# OS-2024-Badge-Schematic-REV0.net
KiCad netlist of a schematic drawn in Altium Designer
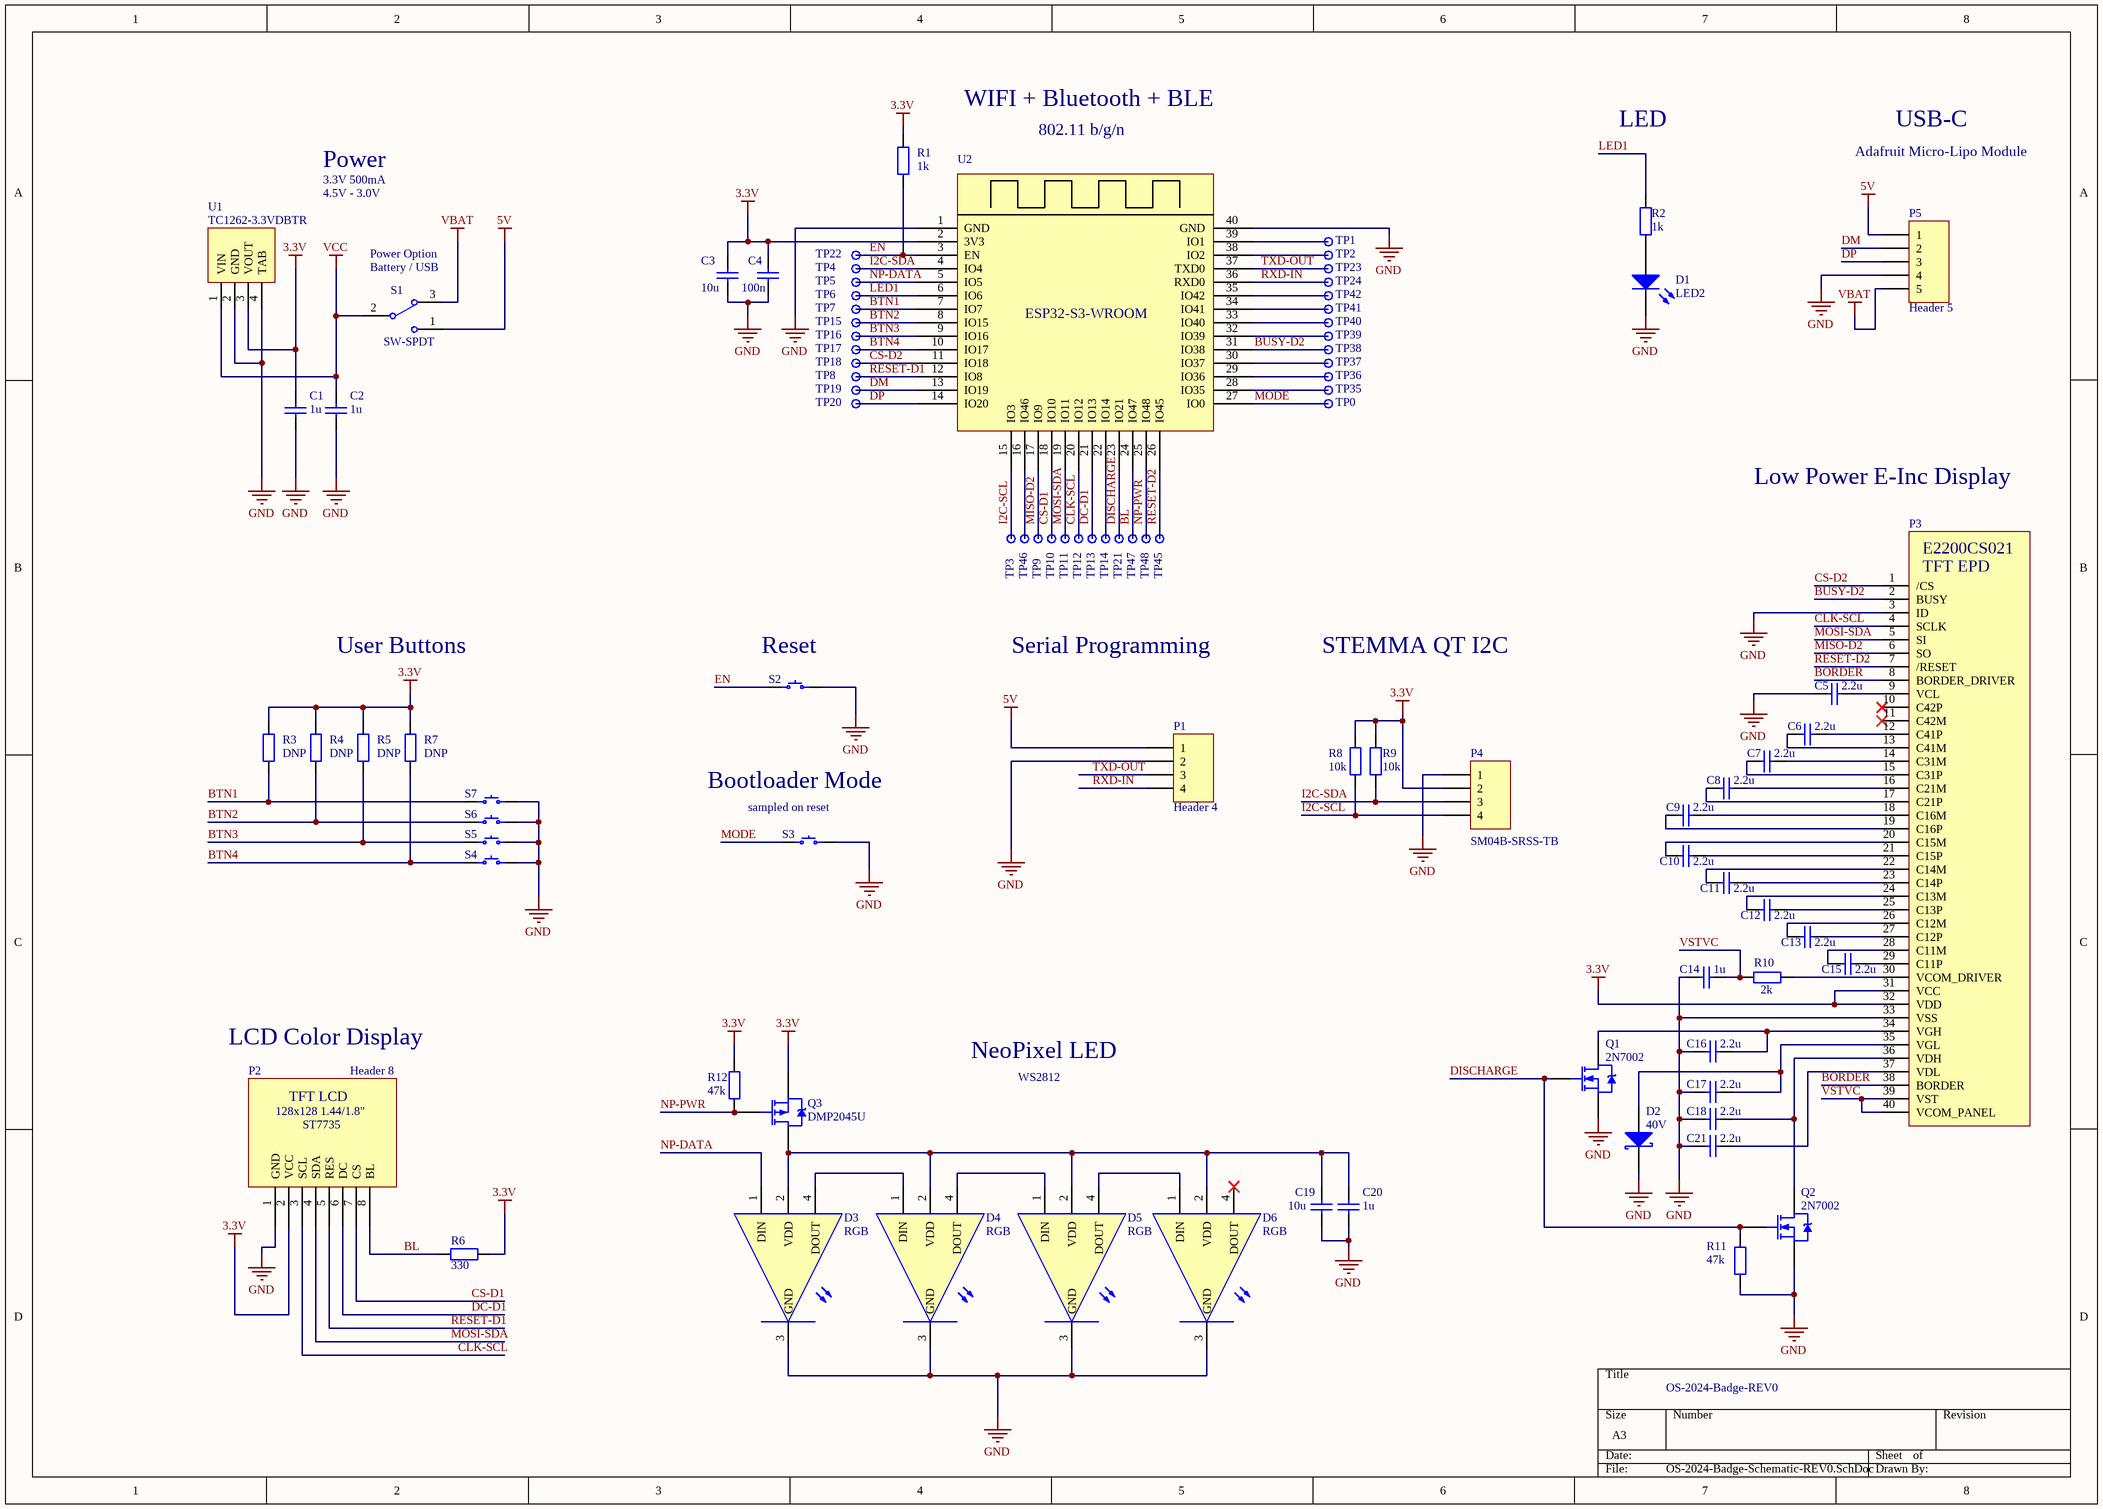
[diagram p0: OS-2024-Badge-Schematic-REV0.SchDoc]

(export (version "E")
  (design (tool "Eeschema 10.0.6"))
  (components
    (comp (ref "C1")
      (value "1u")
      (footprint "0603C")
      (description "CAP CER 1UF 50V Z5U 0603")
      (fields
        (field (name "MANUFACTURER") "Murata Electronics North America")
        (field (name "MANUFACTURER PART NUMBER") "GRT188R61H105ME13D")
      )
      (libsource (lib "Miscellaneous Devices") (part "Cap"))
    )
    (comp (ref "C2")
      (value "1u")
      (footprint "0603C")
      (description "CAP CER 1UF 50V Z5U 0603")
      (fields
        (field (name "MANUFACTURER") "Murata Electronics North America")
        (field (name "MANUFACTURER PART NUMBER") "GRT188R61H105ME13D")
      )
      (libsource (lib "Miscellaneous Devices") (part "Cap"))
    )
    (comp (ref "C3")
      (value "10u")
      (footprint "0603C")
      (description "CAP CER 10UF 10V X5R 0603")
      (fields
        (field (name "MANUFACTURER") "Murata Electronics North America")
        (field (name "MANUFACTURER PART NUMBER") "GRN188R61A106KE69J")
      )
      (libsource (lib "Miscellaneous Devices") (part "Cap"))
    )
    (comp (ref "C4")
      (value "100n")
      (footprint "0603C")
      (description "CAP CER .1UF 10V X7R 0603")
      (fields
        (field (name "MANUFACTURER") "Wurth Electronics Inc.")
        (field (name "MANUFACTURER PART NUMBER") "885012206020")
      )
      (libsource (lib "Miscellaneous Devices") (part "Cap"))
    )
    (comp (ref "C5")
      (value "2.2u")
      (footprint "0603C")
      (description "CAP CER 2.2UF 10V X5R 0603")
      (fields
        (field (name "MANUFACTURER") "Cal-Chip Electronics, Inc.")
        (field (name "MANUFACTURER PART NUMBER") "GMC10X5R225M10NT")
      )
      (libsource (lib "Miscellaneous Devices") (part "Cap"))
    )
    (comp (ref "C6")
      (value "2.2u")
      (footprint "0603C")
      (description "CAP CER 2.2UF 10V X5R 0603")
      (fields
        (field (name "MANUFACTURER") "Cal-Chip Electronics, Inc.")
        (field (name "MANUFACTURER PART NUMBER") "GMC10X5R225M10NT")
      )
      (libsource (lib "Miscellaneous Devices") (part "Cap"))
    )
    (comp (ref "C7")
      (value "2.2u")
      (footprint "0603C")
      (description "CAP CER 2.2UF 10V X5R 0603")
      (fields
        (field (name "MANUFACTURER") "Cal-Chip Electronics, Inc.")
        (field (name "MANUFACTURER PART NUMBER") "GMC10X5R225M10NT")
      )
      (libsource (lib "Miscellaneous Devices") (part "Cap"))
    )
    (comp (ref "C8")
      (value "2.2u")
      (footprint "0603C")
      (description "CAP CER 2.2UF 10V X5R 0603")
      (fields
        (field (name "MANUFACTURER") "Cal-Chip Electronics, Inc.")
        (field (name "MANUFACTURER PART NUMBER") "GMC10X5R225M10NT")
      )
      (libsource (lib "Miscellaneous Devices") (part "Cap"))
    )
    (comp (ref "C9")
      (value "2.2u")
      (footprint "0603C")
      (description "CAP CER 2.2UF 10V X5R 0603")
      (fields
        (field (name "MANUFACTURER") "Cal-Chip Electronics, Inc.")
        (field (name "MANUFACTURER PART NUMBER") "GMC10X5R225M10NT")
      )
      (libsource (lib "Miscellaneous Devices") (part "Cap"))
    )
    (comp (ref "C10")
      (value "2.2u")
      (footprint "0603C")
      (description "CAP CER 2.2UF 10V X5R 0603")
      (fields
        (field (name "MANUFACTURER") "Cal-Chip Electronics, Inc.")
        (field (name "MANUFACTURER PART NUMBER") "GMC10X5R225M10NT")
      )
      (libsource (lib "Miscellaneous Devices") (part "Cap"))
    )
    (comp (ref "C11")
      (value "2.2u")
      (footprint "0603C")
      (description "CAP CER 2.2UF 10V X5R 0603")
      (fields
        (field (name "MANUFACTURER") "Cal-Chip Electronics, Inc.")
        (field (name "MANUFACTURER PART NUMBER") "GMC10X5R225M10NT")
      )
      (libsource (lib "Miscellaneous Devices") (part "Cap"))
    )
    (comp (ref "C12")
      (value "2.2u")
      (footprint "0603C")
      (description "CAP CER 2.2UF 10V X5R 0603")
      (fields
        (field (name "MANUFACTURER") "Cal-Chip Electronics, Inc.")
        (field (name "MANUFACTURER PART NUMBER") "GMC10X5R225M10NT")
      )
      (libsource (lib "Miscellaneous Devices") (part "Cap"))
    )
    (comp (ref "C13")
      (value "2.2u")
      (footprint "0603C")
      (description "CAP CER 2.2UF 10V X5R 0603")
      (fields
        (field (name "MANUFACTURER") "Cal-Chip Electronics, Inc.")
        (field (name "MANUFACTURER PART NUMBER") "GMC10X5R225M10NT")
      )
      (libsource (lib "Miscellaneous Devices") (part "Cap"))
    )
    (comp (ref "C14")
      (value "1u")
      (footprint "0603C")
      (description "CAP CER 1UF 50V Z5U 0603")
      (fields
        (field (name "MANUFACTURER") "Murata Electronics North America")
        (field (name "MANUFACTURER PART NUMBER") "GRT188R61H105ME13D")
      )
      (libsource (lib "Miscellaneous Devices") (part "Cap"))
    )
    (comp (ref "C15")
      (value "2.2u")
      (footprint "0603C")
      (description "CAP CER 2.2UF 10V X5R 0603")
      (fields
        (field (name "MANUFACTURER") "Cal-Chip Electronics, Inc.")
        (field (name "MANUFACTURER PART NUMBER") "GMC10X5R225M10NT")
      )
      (libsource (lib "Miscellaneous Devices") (part "Cap"))
    )
    (comp (ref "C16")
      (value "2.2u")
      (footprint "0603C")
      (description "CAP CER 2.2UF 10V X5R 0603")
      (fields
        (field (name "MANUFACTURER") "Cal-Chip Electronics, Inc.")
        (field (name "MANUFACTURER PART NUMBER") "GMC10X5R225M10NT")
      )
      (libsource (lib "Miscellaneous Devices") (part "Cap"))
    )
    (comp (ref "C17")
      (value "2.2u")
      (footprint "0603C")
      (description "CAP CER 2.2UF 10V X5R 0603")
      (fields
        (field (name "MANUFACTURER") "Cal-Chip Electronics, Inc.")
        (field (name "MANUFACTURER PART NUMBER") "GMC10X5R225M10NT")
      )
      (libsource (lib "Miscellaneous Devices") (part "Cap"))
    )
    (comp (ref "C18")
      (value "2.2u")
      (footprint "0603C")
      (description "CAP CER 2.2UF 10V X5R 0603")
      (fields
        (field (name "MANUFACTURER") "Cal-Chip Electronics, Inc.")
        (field (name "MANUFACTURER PART NUMBER") "GMC10X5R225M10NT")
      )
      (libsource (lib "Miscellaneous Devices") (part "Cap"))
    )
    (comp (ref "C19")
      (value "10u")
      (footprint "0603C")
      (description "CAP CER 10UF 10V X5R 0603")
      (fields
        (field (name "MANUFACTURER") "Murata Electronics North America")
        (field (name "MANUFACTURER PART NUMBER") "GRN188R61A106KE69J")
      )
      (libsource (lib "Miscellaneous Devices") (part "Cap"))
    )
    (comp (ref "C20")
      (value "1u")
      (footprint "0603C")
      (description "CAP CER 1UF 50V Z5U 0603")
      (fields
        (field (name "MANUFACTURER") "Murata Electronics North America")
        (field (name "MANUFACTURER PART NUMBER") "GRT188R61H105ME13D")
      )
      (libsource (lib "Miscellaneous Devices") (part "Cap"))
    )
    (comp (ref "C21")
      (value "2.2u")
      (footprint "0603C")
      (description "CAP CER 2.2UF 10V X5R 0603")
      (fields
        (field (name "MANUFACTURER") "Cal-Chip Electronics, Inc.")
        (field (name "MANUFACTURER PART NUMBER") "GMC10X5R225M10NT")
      )
      (libsource (lib "Miscellaneous Devices") (part "Cap"))
    )
    (comp (ref "D1")
      (value "LED2")
      (footprint "0603LED")
      (description "LED ORANGE CLEAR CHIP SMD")
      (fields
        (field (name "DISTRIBUTOR PART NUMBER") "754-1120-1-ND")
        (field (name "MANUFACTURER") "Kingbright")
      )
      (libsource (lib "Miscellaneous Devices") (part "LED2"))
    )
    (comp (ref "D2")
      (value "40V")
      (footprint "SOD-123FL")
      (description "DIODE SCHOTTKY 40V 2A SOD123FL")
      (fields
        (field (name "DISTRIBUTOR PART NUMBER") "3757-SS2040FL_R1_00001CT-ND")
        (field (name "MANUFACTURER") "Panjit International Inc.")
      )
      (libsource (lib "Miscellaneous Devices") (part "Diode BAT17"))
    )
    (comp (ref "D3")
      (value "RGB")
      (footprint "COM-12986")
      (description "ADDRESS LED DISCR SERIAL RGB")
      (fields
        (field (name "DISTRIBUTOR PART NUMBER") "1568-1213-ND")
        (field (name "MANUFACTURER") "Spark Fun")
      )
      (libsource (lib "2024-Badge-Altium-Project-REV0_1") (part "LED2_1"))
    )
    (comp (ref "D4")
      (value "RGB")
      (footprint "COM-12986")
      (description "ADDRESS LED DISCR SERIAL RGB")
      (fields
        (field (name "DISTRIBUTOR PART NUMBER") "1568-1213-ND")
        (field (name "MANUFACTURER") "Spark Fun")
      )
      (libsource (lib "2024-Badge-Altium-Project-REV0_1") (part "LED2_1"))
    )
    (comp (ref "D5")
      (value "RGB")
      (footprint "COM-12986")
      (description "ADDRESS LED DISCR SERIAL RGB")
      (fields
        (field (name "DISTRIBUTOR PART NUMBER") "1568-1213-ND")
        (field (name "MANUFACTURER") "Spark Fun")
      )
      (libsource (lib "2024-Badge-Altium-Project-REV0_1") (part "LED2_1"))
    )
    (comp (ref "D6")
      (value "RGB")
      (footprint "COM-12986")
      (description "ADDRESS LED DISCR SERIAL RGB")
      (fields
        (field (name "DISTRIBUTOR PART NUMBER") "1568-1213-ND")
        (field (name "MANUFACTURER") "Spark Fun")
      )
      (libsource (lib "2024-Badge-Altium-Project-REV0_1") (part "LED2_1"))
    )
    (comp (ref "P1")
      (value "Header 4")
      (footprint "HDR1X4")
      (description "Header, 4-Pin")
      (fields
        (field (name "DISTRIBUTOR PART NUMBER") "732-5317-ND")
        (field (name "MANUFACTURER") "Wurth Elektronik")
      )
      (libsource (lib "Miscellaneous Connectors") (part "Header 4"))
    )
    (comp (ref "P2")
      (value "Header 8")
      (footprint "TFT144SPI")
      (description "1.44\" 128x128 65K SPI Full Color TFT LCD Display Module ST7735 OLED for Arduino")
      (fields (field (name "DISTRIBUTOR PART NUMBER") "ED90446-ND") (field (name "MANUFACTURER") "Mill-Max"))
      (libsource (lib "OS-2019-Badge-Schematic-REV0") (part "Display_128_128"))
    )
    (comp (ref "P3")
      (value "CONN FPC TOP 40POS 0.5MM R/A")
      (footprint "AMPHENOL_62684-402100ALF")
      (fields
        (field (name "DISTRIBUTOR PART NUMBER") "609-1200-1-ND")
        (field (name "MANUFACTURER") "Amphenol ICC (FCI)")
        (field (name "MANUFACTURER PART NUMBER") "62684-402100ALF")
      )
      (libsource (lib "2024-Badge-Altium-Project-REV0_1") (part "Header 40"))
    )
    (comp (ref "P4")
      (value "SM04B-SRSS-TB")
      (footprint "SM04B-TRSS-TB")
      (description "CONN HEADER SMD R/A 4POS 1MM")
      (fields
        (field (name "DISTRIBUTOR PART NUMBER") "455-SM04B-SRSS-TBCT-ND")
        (field (name "MANUFACTURER") "JST Sales America Inc.")
      )
      (libsource (lib "2024-Badge-Altium-Project-REV0_1") (part "Header 5"))
    )
    (comp (ref "P5")
      (value "Header 5")
      (footprint "Micro-Lipo-USBC")
      (description "Adafruit Micro-Lipo Charger for LiPoly Batt with USB Type C Jack")
      (fields (field (name "DISTRIBUTOR PART NUMBER") "ED90446-ND") (field (name "MANUFACTURER") "Mill-Max"))
      (libsource (lib "Miscellaneous Connectors") (part "Header 5"))
    )
    (comp (ref "Q1")
      (value "2N7002")
      (footprint "SOT-23-N")
      (description "MOSFET N-CH 60V 280MA SOT23-3")
      (fields
        (field (name "DISTRIBUTOR PART NUMBER") "4878-2N7002CT-ND")
        (field (name "MANUFACTURER") "Diotec Semiconductor")
      )
      (libsource (lib "Miscellaneous Devices") (part "NMOS-2"))
    )
    (comp (ref "Q2")
      (value "2N7002")
      (footprint "SOT-23-N")
      (description "MOSFET N-CH 60V 280MA SOT23-3")
      (fields
        (field (name "DISTRIBUTOR PART NUMBER") "4878-2N7002CT-ND")
        (field (name "MANUFACTURER") "Diotec Semiconductor")
      )
      (libsource (lib "Miscellaneous Devices") (part "NMOS-2"))
    )
    (comp (ref "Q3")
      (value "DMP2045U")
      (footprint "SOT-23-P")
      (description "P-Channel Power MOSFET")
      (fields
        (field (name "DISTRIBUTOR PART NUMBER") "DMP2045U-7DICT-ND")
        (field (name "MANUFACTURER") "Diodes Incorporated")
      )
      (libsource (lib "Miscellaneous Devices") (part "PMOS-2"))
    )
    (comp (ref "R1")
      (value "1k")
      (footprint "0603R")
      (description "RES SMD 1K OHM 5% 1/10W 0603")
      (fields
        (field (name "MANUFACTURER") "Yageo")
        (field (name "MANUFACTURER PART NUMBER") "RC0603JR-071KL")
      )
      (libsource (lib "Miscellaneous Devices") (part "Res2"))
    )
    (comp (ref "R2")
      (value "1k")
      (footprint "0603R")
      (description "RES SMD 1K OHM 5% 1/10W 0603")
      (fields
        (field (name "MANUFACTURER") "Yageo")
        (field (name "MANUFACTURER PART NUMBER") "RC0603JR-071KL")
      )
      (libsource (lib "") (part "Res2_2"))
    )
    (comp (ref "R3")
      (value "DNP")
      (footprint "0603R")
      (description "RES SMD 1K OHM 5% 1/10W 0603")
      (fields (field (name "MANUFACTURER") "NONE"))
      (libsource (lib "Miscellaneous Devices") (part "Res2"))
    )
    (comp (ref "R4")
      (value "DNP")
      (footprint "0603R")
      (description "RES SMD 1K OHM 5% 1/10W 0603")
      (fields (field (name "MANUFACTURER") "NONE"))
      (libsource (lib "Miscellaneous Devices") (part "Res2"))
    )
    (comp (ref "R5")
      (value "DNP")
      (footprint "0603R")
      (description "RES SMD 1K OHM 5% 1/10W 0603")
      (fields (field (name "MANUFACTURER") "NONE"))
      (libsource (lib "Miscellaneous Devices") (part "Res2"))
    )
    (comp (ref "R6")
      (value "330")
      (footprint "0603R")
      (description "RES SMD 330 OHM 5% 1/10W 0603")
      (fields
        (field (name "MANUFACTURER") "Yageo")
        (field (name "MANUFACTURER PART NUMBER") "RC0603JR-07330RL")
      )
      (libsource (lib "") (part "Res2_1"))
    )
    (comp (ref "R7")
      (value "DNP")
      (footprint "0603R")
      (description "RES SMD 1K OHM 5% 1/10W 0603")
      (fields (field (name "MANUFACTURER") "NONE"))
      (libsource (lib "Miscellaneous Devices") (part "Res2"))
    )
    (comp (ref "R8")
      (value "10k")
      (footprint "0603R")
      (description "RES SMD 47K OHM 5% 1/10W 0603")
      (fields
        (field (name "MANUFACTURER") "Yageo")
        (field (name "MANUFACTURER PART NUMBER") "RC0603JR-0710KL")
      )
      (libsource (lib "") (part "Res2_2"))
    )
    (comp (ref "R9")
      (value "10k")
      (footprint "0603R")
      (description "RES SMD 47K OHM 5% 1/10W 0603")
      (fields
        (field (name "MANUFACTURER") "Yageo")
        (field (name "MANUFACTURER PART NUMBER") "RC0603JR-0710KL")
      )
      (libsource (lib "") (part "Res2_2"))
    )
    (comp (ref "R10")
      (value "2k")
      (footprint "0603R")
      (description "RES SMD 1K OHM 5% 1/10W 0603")
      (fields
        (field (name "MANUFACTURER") "Yageo")
        (field (name "MANUFACTURER PART NUMBER") "RC0603JR-072KL")
      )
      (libsource (lib "") (part "Res2_1"))
    )
    (comp (ref "R11")
      (value "47k")
      (footprint "0603R")
      (description "RES SMD 47K OHM 5% 1/10W 0603")
      (fields
        (field (name "MANUFACTURER") "Yageo")
        (field (name "MANUFACTURER PART NUMBER") "RC0603JR-0747KL")
      )
      (libsource (lib "") (part "Res2_2"))
    )
    (comp (ref "R12")
      (value "47k")
      (footprint "0603R")
      (description "RES SMD 47K OHM 5% 1/10W 0603")
      (fields
        (field (name "MANUFACTURER") "Yageo")
        (field (name "MANUFACTURER PART NUMBER") "RC0603JR-0747KL")
      )
      (libsource (lib "") (part "Res2_2"))
    )
    (comp (ref "S1")
      (value "SW-SPDT")
      (footprint "HDR1X3")
      (description "SPDT Subminiature Toggle Switch, Right Angle Mounting, Vertical Actuation")
      (fields (field (name "MANUFACTURER") "E-Switch") (field (name "MANUFACTURER PART NUMBER") "EG1903-ND"))
      (libsource (lib "Miscellaneous Devices") (part "SW-SPDT"))
    )
    (comp (ref "S2")
      (value "SPST-NO")
      (footprint "PTS636SL43LFS")
      (description "Tactile Switch SPST-NO Top Actuated Through Hole")
      (fields (field (name "DISTRIBUTOR PART NUMBER") "CKN12301-ND") (field (name "MANUFACTURER") "C&K"))
      (libsource (lib "Button") (part "SPST-NO 2 PIN"))
    )
    (comp (ref "S3")
      (value "SPST-NO")
      (footprint "PTS636SL43LFS")
      (description "Tactile Switch SPST-NO Top Actuated Through Hole")
      (fields (field (name "DISTRIBUTOR PART NUMBER") "CKN12301-ND") (field (name "MANUFACTURER") "C&K"))
      (libsource (lib "Button") (part "SPST-NO 2 PIN"))
    )
    (comp (ref "S4")
      (value "SPST-NO")
      (footprint "PTS636SL43LFS")
      (description "Tactile Switch SPST-NO Top Actuated Through Hole")
      (fields (field (name "DISTRIBUTOR PART NUMBER") "CKN12301-ND") (field (name "MANUFACTURER") "C&K"))
      (libsource (lib "Button") (part "SPST-NO 2 PIN"))
    )
    (comp (ref "S5")
      (value "SPST-NO")
      (footprint "PTS636SL43LFS")
      (description "Tactile Switch SPST-NO Top Actuated Through Hole")
      (fields (field (name "DISTRIBUTOR PART NUMBER") "CKN12301-ND") (field (name "MANUFACTURER") "C&K"))
      (libsource (lib "Button") (part "SPST-NO 2 PIN"))
    )
    (comp (ref "S6")
      (value "SPST-NO")
      (footprint "PTS636SL43LFS")
      (description "Tactile Switch SPST-NO Top Actuated Through Hole")
      (fields (field (name "DISTRIBUTOR PART NUMBER") "CKN12301-ND") (field (name "MANUFACTURER") "C&K"))
      (libsource (lib "Button") (part "SPST-NO 2 PIN"))
    )
    (comp (ref "S7")
      (value "SPST-NO")
      (footprint "PTS636SL43LFS")
      (description "Tactile Switch SPST-NO Top Actuated Through Hole")
      (fields (field (name "DISTRIBUTOR PART NUMBER") "CKN12301-ND") (field (name "MANUFACTURER") "C&K"))
      (libsource (lib "Button") (part "SPST-NO 2 PIN"))
    )
    (comp (ref "TP0")
      (value "Test Point")
      (footprint "Testpoint")
      (description "Test Point Do Not Populate")
      (fields (field (name "MANUFACTURER") "NONE"))
      (libsource (lib "*") (part "TestPoint"))
    )
    (comp (ref "TP1")
      (value "Test Point")
      (footprint "Testpoint")
      (description "Test Point Do Not Populate")
      (fields (field (name "MANUFACTURER") "NONE"))
      (libsource (lib "*") (part "TestPoint"))
    )
    (comp (ref "TP2")
      (value "Test Point")
      (footprint "Testpoint")
      (description "Test Point Do Not Populate")
      (fields (field (name "MANUFACTURER") "NONE"))
      (libsource (lib "*") (part "TestPoint"))
    )
    (comp (ref "TP3")
      (value "Test Point")
      (footprint "Testpoint")
      (description "Test Point Do Not Populate")
      (fields (field (name "MANUFACTURER") "NONE"))
      (libsource (lib "*") (part "TestPoint"))
    )
    (comp (ref "TP4")
      (value "Test Point")
      (footprint "Testpoint")
      (description "Test Point Do Not Populate")
      (fields (field (name "MANUFACTURER") "NONE"))
      (libsource (lib "*") (part "TestPoint"))
    )
    (comp (ref "TP5")
      (value "Test Point")
      (footprint "Testpoint")
      (description "Test Point Do Not Populate")
      (fields (field (name "MANUFACTURER") "NONE"))
      (libsource (lib "*") (part "TestPoint"))
    )
    (comp (ref "TP6")
      (value "Test Point")
      (footprint "Testpoint")
      (description "Test Point Do Not Populate")
      (fields (field (name "MANUFACTURER") "NONE"))
      (libsource (lib "*") (part "TestPoint"))
    )
    (comp (ref "TP7")
      (value "Test Point")
      (footprint "Testpoint")
      (description "Test Point Do Not Populate")
      (fields (field (name "MANUFACTURER") "NONE"))
      (libsource (lib "*") (part "TestPoint"))
    )
    (comp (ref "TP8")
      (value "Test Point")
      (footprint "Testpoint")
      (description "Test Point Do Not Populate")
      (fields (field (name "MANUFACTURER") "NONE"))
      (libsource (lib "*") (part "TestPoint"))
    )
    (comp (ref "TP9")
      (value "Test Point")
      (footprint "Testpoint")
      (description "Test Point Do Not Populate")
      (fields (field (name "MANUFACTURER") "NONE"))
      (libsource (lib "*") (part "TestPoint"))
    )
    (comp (ref "TP10")
      (value "Test Point")
      (footprint "Testpoint")
      (description "Test Point Do Not Populate")
      (fields (field (name "MANUFACTURER") "NONE"))
      (libsource (lib "*") (part "TestPoint"))
    )
    (comp (ref "TP11")
      (value "Test Point")
      (footprint "Testpoint")
      (description "Test Point Do Not Populate")
      (fields (field (name "MANUFACTURER") "NONE"))
      (libsource (lib "*") (part "TestPoint"))
    )
    (comp (ref "TP12")
      (value "Test Point")
      (footprint "Testpoint")
      (description "Test Point Do Not Populate")
      (fields (field (name "MANUFACTURER") "NONE"))
      (libsource (lib "*") (part "TestPoint"))
    )
    (comp (ref "TP13")
      (value "Test Point")
      (footprint "Testpoint")
      (description "Test Point Do Not Populate")
      (fields (field (name "MANUFACTURER") "NONE"))
      (libsource (lib "*") (part "TestPoint"))
    )
    (comp (ref "TP14")
      (value "Test Point")
      (footprint "Testpoint")
      (description "Test Point Do Not Populate")
      (fields (field (name "MANUFACTURER") "NONE"))
      (libsource (lib "*") (part "TestPoint"))
    )
    (comp (ref "TP15")
      (value "Test Point")
      (footprint "Testpoint")
      (description "Test Point Do Not Populate")
      (fields (field (name "MANUFACTURER") "NONE"))
      (libsource (lib "*") (part "TestPoint"))
    )
    (comp (ref "TP16")
      (value "Test Point")
      (footprint "Testpoint")
      (description "Test Point Do Not Populate")
      (fields (field (name "MANUFACTURER") "NONE"))
      (libsource (lib "*") (part "TestPoint"))
    )
    (comp (ref "TP17")
      (value "Test Point")
      (footprint "Testpoint")
      (description "Test Point Do Not Populate")
      (fields (field (name "MANUFACTURER") "NONE"))
      (libsource (lib "*") (part "TestPoint"))
    )
    (comp (ref "TP18")
      (value "Test Point")
      (footprint "Testpoint")
      (description "Test Point Do Not Populate")
      (fields (field (name "MANUFACTURER") "NONE"))
      (libsource (lib "*") (part "TestPoint"))
    )
    (comp (ref "TP19")
      (value "Test Point")
      (footprint "Testpoint")
      (description "Test Point Do Not Populate")
      (fields (field (name "MANUFACTURER") "NONE"))
      (libsource (lib "*") (part "TestPoint"))
    )
    (comp (ref "TP20")
      (value "Test Point")
      (footprint "Testpoint")
      (description "Test Point Do Not Populate")
      (fields (field (name "MANUFACTURER") "NONE"))
      (libsource (lib "*") (part "TestPoint"))
    )
    (comp (ref "TP21")
      (value "Test Point")
      (footprint "Testpoint")
      (description "Test Point Do Not Populate")
      (fields (field (name "MANUFACTURER") "NONE"))
      (libsource (lib "*") (part "TestPoint"))
    )
    (comp (ref "TP22")
      (value "Test Point")
      (footprint "Testpoint")
      (description "Test Point Do Not Populate")
      (fields (field (name "MANUFACTURER") "NONE"))
      (libsource (lib "*") (part "TestPoint"))
    )
    (comp (ref "TP23")
      (value "Test Point")
      (footprint "Testpoint")
      (description "Test Point Do Not Populate")
      (fields (field (name "MANUFACTURER") "NONE"))
      (libsource (lib "*") (part "TestPoint"))
    )
    (comp (ref "TP24")
      (value "Test Point")
      (footprint "Testpoint")
      (description "Test Point Do Not Populate")
      (fields (field (name "MANUFACTURER") "NONE"))
      (libsource (lib "*") (part "TestPoint"))
    )
    (comp (ref "TP35")
      (value "Test Point")
      (footprint "Testpoint")
      (description "Test Point Do Not Populate")
      (fields (field (name "MANUFACTURER") "NONE"))
      (libsource (lib "*") (part "TestPoint"))
    )
    (comp (ref "TP36")
      (value "Test Point")
      (footprint "Testpoint")
      (description "Test Point Do Not Populate")
      (fields (field (name "MANUFACTURER") "NONE"))
      (libsource (lib "*") (part "TestPoint"))
    )
    (comp (ref "TP37")
      (value "Test Point")
      (footprint "Testpoint")
      (description "Test Point Do Not Populate")
      (fields (field (name "MANUFACTURER") "NONE"))
      (libsource (lib "*") (part "TestPoint"))
    )
    (comp (ref "TP38")
      (value "Test Point")
      (footprint "Testpoint")
      (description "Test Point Do Not Populate")
      (fields (field (name "MANUFACTURER") "NONE"))
      (libsource (lib "*") (part "TestPoint"))
    )
    (comp (ref "TP39")
      (value "Test Point")
      (footprint "Testpoint")
      (description "Test Point Do Not Populate")
      (fields (field (name "MANUFACTURER") "NONE"))
      (libsource (lib "*") (part "TestPoint"))
    )
    (comp (ref "TP40")
      (value "Test Point")
      (footprint "Testpoint")
      (description "Test Point Do Not Populate")
      (fields (field (name "MANUFACTURER") "NONE"))
      (libsource (lib "*") (part "TestPoint"))
    )
    (comp (ref "TP41")
      (value "Test Point")
      (footprint "Testpoint")
      (description "Test Point Do Not Populate")
      (fields (field (name "MANUFACTURER") "NONE"))
      (libsource (lib "*") (part "TestPoint"))
    )
    (comp (ref "TP42")
      (value "Test Point")
      (footprint "Testpoint")
      (description "Test Point Do Not Populate")
      (fields (field (name "MANUFACTURER") "NONE"))
      (libsource (lib "*") (part "TestPoint"))
    )
    (comp (ref "TP45")
      (value "Test Point")
      (footprint "Testpoint")
      (description "Test Point Do Not Populate")
      (fields (field (name "MANUFACTURER") "NONE"))
      (libsource (lib "*") (part "TestPoint"))
    )
    (comp (ref "TP46")
      (value "Test Point")
      (footprint "Testpoint")
      (description "Test Point Do Not Populate")
      (fields (field (name "MANUFACTURER") "NONE"))
      (libsource (lib "*") (part "TestPoint"))
    )
    (comp (ref "TP47")
      (value "Test Point")
      (footprint "Testpoint")
      (description "Test Point Do Not Populate")
      (fields (field (name "MANUFACTURER") "NONE"))
      (libsource (lib "*") (part "TestPoint"))
    )
    (comp (ref "TP48")
      (value "Test Point")
      (footprint "Testpoint")
      (description "Test Point Do Not Populate")
      (fields (field (name "MANUFACTURER") "NONE"))
      (libsource (lib "*") (part "TestPoint"))
    )
    (comp (ref "U1")
      (value "TC1262-3.3VDBTR")
      (footprint "OS-2019-Badge-REV0:SOT-223-2")
      (description "IC REG LINEAR 3.3V 500mA SOT223-3")
      (fields
        (field (name "MANUFACTURER") "Microchip Technology")
        (field (name "DISTRIBUTOR PART NUMBER") "TC1262-3.3VDBCT-ND")
      )
      (libsource (lib "OS-2019-Badge-Schematic-REV0") (part "Header 3"))
    )
    (comp (ref "U2")
      (value "ESP32-S3-WROOM")
      (footprint "ESP32-S3-WROOM-1-N16R8")
      (description "Bluetooth, WiFi 802.11b/g/n, Bluetooth v5.0 Transceiver Module 2.4GHz PCB Trace Surface Mount")
      (fields
        (field (name "MANUFACTURER") "Espressif Systems")
        (field (name "MANUFACTURER PART NUMBER") "ESP32-S3-WROOM-1-N16R8")
      )
      (libsource (lib "2024-Badge-Altium-Project-REV0_1") (part "ESP32-S3-WROOM"))
    )
  )
  (nets
    (net (code "1") (name "/BL") (class "Default")
      (node (ref "P2") (pin "8") (pinfunction "BL_8") (pintype "passive"))
      (node (ref "R6") (pin "1") (pinfunction "1_1") (pintype "passive"))
      (node (ref "TP47") (pin "1") (pinfunction "1_1") (pintype "passive"))
      (node (ref "U2") (pin "24") (pinfunction "IO47_24") (pintype "passive"))
    )
    (net (code "2") (name "/BORDER") (class "Default")
      (node (ref "P3") (pin "38") (pinfunction "BORDER_38") (pintype "passive"))
      (node (ref "P3") (pin "8") (pinfunction "BORDER_DRIVER_8") (pintype "passive"))
    )
    (net (code "3") (name "/BTN1") (class "Default")
      (node (ref "R3") (pin "1") (pinfunction "1_1") (pintype "passive"))
      (node (ref "S7") (pin "1") (pinfunction "1_1") (pintype "passive"))
      (node (ref "TP7") (pin "1") (pinfunction "1_1") (pintype "passive"))
      (node (ref "U2") (pin "7") (pinfunction "IO7_7") (pintype "passive"))
    )
    (net (code "4") (name "/BTN2") (class "Default")
      (node (ref "R4") (pin "1") (pinfunction "1_1") (pintype "passive"))
      (node (ref "S6") (pin "1") (pinfunction "1_1") (pintype "passive"))
      (node (ref "TP15") (pin "1") (pinfunction "1_1") (pintype "passive"))
      (node (ref "U2") (pin "8") (pinfunction "IO15_8") (pintype "passive"))
    )
    (net (code "5") (name "/BTN3") (class "Default")
      (node (ref "R5") (pin "1") (pinfunction "1_1") (pintype "passive"))
      (node (ref "S5") (pin "1") (pinfunction "1_1") (pintype "passive"))
      (node (ref "TP16") (pin "1") (pinfunction "1_1") (pintype "passive"))
      (node (ref "U2") (pin "9") (pinfunction "IO16_9") (pintype "passive"))
    )
    (net (code "6") (name "/BTN4") (class "Default")
      (node (ref "R7") (pin "1") (pinfunction "1_1") (pintype "passive"))
      (node (ref "S4") (pin "1") (pinfunction "1_1") (pintype "passive"))
      (node (ref "TP17") (pin "1") (pinfunction "1_1") (pintype "passive"))
      (node (ref "U2") (pin "10") (pinfunction "IO17_10") (pintype "passive"))
    )
    (net (code "7") (name "/BUSY-D2") (class "Default")
      (node (ref "P3") (pin "2") (pinfunction "BUSY_2") (pintype "passive"))
      (node (ref "TP38") (pin "1") (pinfunction "1_1") (pintype "passive"))
      (node (ref "U2") (pin "31") (pinfunction "IO38_31") (pintype "passive"))
    )
    (net (code "8") (name "/CLK-SCL") (class "Default")
      (node (ref "P2") (pin "3") (pinfunction "SCL_3") (pintype "passive"))
      (node (ref "P3") (pin "4") (pinfunction "SCLK_4") (pintype "passive"))
      (node (ref "TP12") (pin "1") (pinfunction "1_1") (pintype "passive"))
      (node (ref "U2") (pin "20") (pinfunction "IO12_20") (pintype "passive"))
    )
    (net (code "9") (name "/CS-D1") (class "Default")
      (node (ref "P2") (pin "7") (pinfunction "CS_7") (pintype "passive"))
      (node (ref "TP10") (pin "1") (pinfunction "1_1") (pintype "passive"))
      (node (ref "U2") (pin "18") (pinfunction "IO10_18") (pintype "passive"))
    )
    (net (code "10") (name "/CS-D2") (class "Default")
      (node (ref "P3") (pin "1") (pinfunction "/CS_1") (pintype "passive"))
      (node (ref "TP18") (pin "1") (pinfunction "1_1") (pintype "passive"))
      (node (ref "U2") (pin "11") (pinfunction "IO18_11") (pintype "passive"))
    )
    (net (code "11") (name "/DC-D1") (class "Default")
      (node (ref "P2") (pin "6") (pinfunction "DC_6") (pintype "passive"))
      (node (ref "TP13") (pin "1") (pinfunction "1_1") (pintype "passive"))
      (node (ref "U2") (pin "21") (pinfunction "IO13_21") (pintype "passive"))
    )
    (net (code "12") (name "/DISCHARGE") (class "Default")
      (node (ref "Q1") (pin "1") (pinfunction "G_1") (pintype "passive"))
      (node (ref "Q2") (pin "1") (pinfunction "G_1") (pintype "passive"))
      (node (ref "R11") (pin "1") (pinfunction "1_1") (pintype "passive"))
      (node (ref "TP21") (pin "1") (pinfunction "1_1") (pintype "passive"))
      (node (ref "U2") (pin "23") (pinfunction "IO21_23") (pintype "passive"))
    )
    (net (code "13") (name "/DM") (class "Default")
      (node (ref "P5") (pin "2") (pinfunction "2_2") (pintype "passive"))
      (node (ref "TP19") (pin "1") (pinfunction "1_1") (pintype "passive"))
      (node (ref "U2") (pin "13") (pinfunction "IO19_13") (pintype "passive"))
    )
    (net (code "14") (name "/DP") (class "Default")
      (node (ref "P5") (pin "3") (pinfunction "3_3") (pintype "passive"))
      (node (ref "TP20") (pin "1") (pinfunction "1_1") (pintype "passive"))
      (node (ref "U2") (pin "14") (pinfunction "IO20_14") (pintype "passive"))
    )
    (net (code "15") (name "/EN") (class "Default")
      (node (ref "R1") (pin "1") (pinfunction "1_1") (pintype "passive"))
      (node (ref "S2") (pin "1") (pinfunction "1_1") (pintype "passive"))
      (node (ref "TP22") (pin "1") (pinfunction "1_1") (pintype "passive"))
      (node (ref "U2") (pin "3") (pinfunction "EN_3") (pintype "passive"))
    )
    (net (code "16") (name "/I2C-SCL") (class "Default")
      (node (ref "P4") (pin "4") (pinfunction "4_4") (pintype "passive"))
      (node (ref "R8") (pin "2") (pinfunction "2_2") (pintype "passive"))
      (node (ref "TP3") (pin "1") (pinfunction "1_1") (pintype "passive"))
      (node (ref "U2") (pin "15") (pinfunction "IO3_15") (pintype "passive"))
    )
    (net (code "17") (name "/I2C-SDA") (class "Default")
      (node (ref "P4") (pin "3") (pinfunction "3_3") (pintype "passive"))
      (node (ref "R9") (pin "2") (pinfunction "2_2") (pintype "passive"))
      (node (ref "TP4") (pin "1") (pinfunction "1_1") (pintype "passive"))
      (node (ref "U2") (pin "4") (pinfunction "IO4_4") (pintype "passive"))
    )
    (net (code "18") (name "/LED1") (class "Default")
      (node (ref "R2") (pin "1") (pinfunction "1_1") (pintype "passive"))
      (node (ref "TP6") (pin "1") (pinfunction "1_1") (pintype "passive"))
      (node (ref "U2") (pin "6") (pinfunction "IO6_6") (pintype "passive"))
    )
    (net (code "19") (name "/MISO-D2") (class "Default")
      (node (ref "P3") (pin "6") (pinfunction "SO_6") (pintype "passive"))
      (node (ref "TP9") (pin "1") (pinfunction "1_1") (pintype "passive"))
      (node (ref "U2") (pin "17") (pinfunction "IO9_17") (pintype "passive"))
    )
    (net (code "20") (name "/MODE") (class "Default")
      (node (ref "S3") (pin "1") (pinfunction "1_1") (pintype "passive"))
      (node (ref "TP0") (pin "1") (pinfunction "1_1") (pintype "passive"))
      (node (ref "U2") (pin "27") (pinfunction "IO0_27") (pintype "passive"))
    )
    (net (code "21") (name "/MOSI-SDA") (class "Default")
      (node (ref "P2") (pin "4") (pinfunction "SDA_4") (pintype "passive"))
      (node (ref "P3") (pin "5") (pinfunction "SI_5") (pintype "passive"))
      (node (ref "TP11") (pin "1") (pinfunction "1_1") (pintype "passive"))
      (node (ref "U2") (pin "19") (pinfunction "IO11_19") (pintype "passive"))
    )
    (net (code "22") (name "/NP-DATA") (class "Default")
      (node (ref "D3") (pin "1") (pinfunction "DIN_1") (pintype "passive"))
      (node (ref "TP5") (pin "1") (pinfunction "1_1") (pintype "passive"))
      (node (ref "U2") (pin "5") (pinfunction "IO5_5") (pintype "passive"))
    )
    (net (code "23") (name "/NP-PWR") (class "Default")
      (node (ref "Q3") (pin "G") (pinfunction "G_G") (pintype "passive"))
      (node (ref "R12") (pin "2") (pinfunction "2_2") (pintype "passive"))
      (node (ref "TP48") (pin "1") (pinfunction "1_1") (pintype "passive"))
      (node (ref "U2") (pin "25") (pinfunction "IO48_25") (pintype "passive"))
    )
    (net (code "24") (name "/RESET-D1") (class "Default")
      (node (ref "P2") (pin "5") (pinfunction "RES_5") (pintype "passive"))
      (node (ref "TP8") (pin "1") (pinfunction "1_1") (pintype "passive"))
      (node (ref "U2") (pin "12") (pinfunction "IO8_12") (pintype "passive"))
    )
    (net (code "25") (name "/RESET-D2") (class "Default")
      (node (ref "P3") (pin "7") (pinfunction "/RESET_7") (pintype "passive"))
      (node (ref "TP45") (pin "1") (pinfunction "1_1") (pintype "passive"))
      (node (ref "U2") (pin "26") (pinfunction "IO45_26") (pintype "passive"))
    )
    (net (code "26") (name "/RXD-IN") (class "Default")
      (node (ref "P1") (pin "4") (pinfunction "4_4") (pintype "passive"))
      (node (ref "TP24") (pin "1") (pinfunction "1_1") (pintype "passive"))
      (node (ref "U2") (pin "36") (pinfunction "RXD0_36") (pintype "passive"))
    )
    (net (code "27") (name "/TXD-OUT") (class "Default")
      (node (ref "P1") (pin "3") (pinfunction "3_3") (pintype "passive"))
      (node (ref "TP23") (pin "1") (pinfunction "1_1") (pintype "passive"))
      (node (ref "U2") (pin "37") (pinfunction "TXD0_37") (pintype "passive"))
    )
    (net (code "28") (name "/VSTVC") (class "Default")
      (node (ref "C14") (pin "2") (pinfunction "2_2") (pintype "passive"))
      (node (ref "P3") (pin "39") (pinfunction "VST_39") (pintype "passive"))
      (node (ref "P3") (pin "40") (pinfunction "VCOM_PANEL_40") (pintype "passive"))
      (node (ref "R10") (pin "1") (pinfunction "1_1") (pintype "passive"))
    )
    (net (code "29") (name "3.3V") (class "Default")
      (node (ref "C1") (pin "1") (pinfunction "1_1") (pintype "passive"))
      (node (ref "C3") (pin "1") (pinfunction "1_1") (pintype "passive"))
      (node (ref "C4") (pin "1") (pinfunction "1_1") (pintype "passive"))
      (node (ref "P2") (pin "2") (pinfunction "VCC_2") (pintype "passive"))
      (node (ref "P3") (pin "31") (pinfunction "VCC_31") (pintype "passive"))
      (node (ref "P3") (pin "32") (pinfunction "VDD_32") (pintype "passive"))
      (node (ref "P4") (pin "2") (pinfunction "2_2") (pintype "passive"))
      (node (ref "Q3") (pin "S") (pinfunction "S_S") (pintype "passive"))
      (node (ref "R1") (pin "2") (pinfunction "2_2") (pintype "passive"))
      (node (ref "R12") (pin "1") (pinfunction "1_1") (pintype "passive"))
      (node (ref "R3") (pin "2") (pinfunction "2_2") (pintype "passive"))
      (node (ref "R4") (pin "2") (pinfunction "2_2") (pintype "passive"))
      (node (ref "R5") (pin "2") (pinfunction "2_2") (pintype "passive"))
      (node (ref "R6") (pin "2") (pinfunction "2_2") (pintype "passive"))
      (node (ref "R7") (pin "2") (pinfunction "2_2") (pintype "passive"))
      (node (ref "R8") (pin "1") (pinfunction "1_1") (pintype "passive"))
      (node (ref "R9") (pin "1") (pinfunction "1_1") (pintype "passive"))
      (node (ref "U1") (pin "3") (pinfunction "VOUT_3") (pintype "passive"))
      (node (ref "U2") (pin "2") (pinfunction "3V3_2") (pintype "passive"))
    )
    (net (code "30") (name "5V") (class "Default")
      (node (ref "P1") (pin "1") (pinfunction "1_1") (pintype "passive"))
      (node (ref "P5") (pin "1") (pinfunction "1_1") (pintype "passive"))
      (node (ref "S1") (pin "1") (pinfunction "1_1") (pintype "passive"))
    )
    (net (code "31") (name "GND") (class "Default")
      (node (ref "C1") (pin "2") (pinfunction "2_2") (pintype "passive"))
      (node (ref "C14") (pin "1") (pinfunction "1_1") (pintype "passive"))
      (node (ref "C16") (pin "2") (pinfunction "2_2") (pintype "passive"))
      (node (ref "C17") (pin "2") (pinfunction "2_2") (pintype "passive"))
      (node (ref "C18") (pin "2") (pinfunction "2_2") (pintype "passive"))
      (node (ref "C19") (pin "2") (pinfunction "2_2") (pintype "passive"))
      (node (ref "C2") (pin "2") (pinfunction "2_2") (pintype "passive"))
      (node (ref "C20") (pin "2") (pinfunction "2_2") (pintype "passive"))
      (node (ref "C21") (pin "2") (pinfunction "2_2") (pintype "passive"))
      (node (ref "C3") (pin "2") (pinfunction "2_2") (pintype "passive"))
      (node (ref "C4") (pin "2") (pinfunction "2_2") (pintype "passive"))
      (node (ref "C5") (pin "1") (pinfunction "1_1") (pintype "passive"))
      (node (ref "D1") (pin "2") (pinfunction "K_2") (pintype "passive"))
      (node (ref "D2") (pin "1") (pinfunction "K_1") (pintype "passive"))
      (node (ref "D3") (pin "3") (pinfunction "GND_3") (pintype "passive"))
      (node (ref "D4") (pin "3") (pinfunction "GND_3") (pintype "passive"))
      (node (ref "D5") (pin "3") (pinfunction "GND_3") (pintype "passive"))
      (node (ref "D6") (pin "3") (pinfunction "GND_3") (pintype "passive"))
      (node (ref "P1") (pin "2") (pinfunction "2_2") (pintype "passive"))
      (node (ref "P2") (pin "1") (pinfunction "GND_1") (pintype "passive"))
      (node (ref "P3") (pin "3") (pinfunction "ID_3") (pintype "passive"))
      (node (ref "P3") (pin "33") (pinfunction "VSS_33") (pintype "passive"))
      (node (ref "P4") (pin "1") (pinfunction "1_1") (pintype "passive"))
      (node (ref "P5") (pin "4") (pinfunction "4_4") (pintype "passive"))
      (node (ref "Q1") (pin "2") (pinfunction "S_2") (pintype "passive"))
      (node (ref "Q2") (pin "2") (pinfunction "S_2") (pintype "passive"))
      (node (ref "R11") (pin "2") (pinfunction "2_2") (pintype "passive"))
      (node (ref "S2") (pin "2") (pinfunction "2_2") (pintype "passive"))
      (node (ref "S3") (pin "2") (pinfunction "2_2") (pintype "passive"))
      (node (ref "S4") (pin "2") (pinfunction "2_2") (pintype "passive"))
      (node (ref "S5") (pin "2") (pinfunction "2_2") (pintype "passive"))
      (node (ref "S6") (pin "2") (pinfunction "2_2") (pintype "passive"))
      (node (ref "S7") (pin "2") (pinfunction "2_2") (pintype "passive"))
      (node (ref "U1") (pin "2") (pinfunction "GND_2") (pintype "passive"))
      (node (ref "U1") (pin "4") (pinfunction "TAB_4") (pintype "passive"))
      (node (ref "U2") (pin "1") (pinfunction "GND_1") (pintype "passive"))
      (node (ref "U2") (pin "40") (pinfunction "GND_40") (pintype "passive"))
    )
    (net (code "32") (name "Net-(D1-A)") (class "Default")
      (node (ref "D1") (pin "1") (pinfunction "A_1") (pintype "passive"))
      (node (ref "R2") (pin "2") (pinfunction "2_2") (pintype "passive"))
    )
    (net (code "33") (name "Net-(D2-A)") (class "Default")
      (node (ref "C17") (pin "1") (pinfunction "1_1") (pintype "passive"))
      (node (ref "D2") (pin "2") (pinfunction "A_2") (pintype "passive"))
      (node (ref "P3") (pin "35") (pinfunction "VGL_35") (pintype "passive"))
    )
    (net (code "34") (name "Net-(D3-DOUT)") (class "Default")
      (node (ref "D3") (pin "4") (pinfunction "DOUT_4") (pintype "passive"))
      (node (ref "D4") (pin "1") (pinfunction "DIN_1") (pintype "passive"))
    )
    (net (code "35") (name "Net-(D3-VDD)") (class "Default")
      (node (ref "C19") (pin "1") (pinfunction "1_1") (pintype "passive"))
      (node (ref "C20") (pin "1") (pinfunction "1_1") (pintype "passive"))
      (node (ref "D3") (pin "2") (pinfunction "VDD_2") (pintype "passive"))
      (node (ref "D4") (pin "2") (pinfunction "VDD_2") (pintype "passive"))
      (node (ref "D5") (pin "2") (pinfunction "VDD_2") (pintype "passive"))
      (node (ref "D6") (pin "2") (pinfunction "VDD_2") (pintype "passive"))
      (node (ref "Q3") (pin "D") (pinfunction "D_D") (pintype "passive"))
    )
    (net (code "36") (name "Net-(D4-DOUT)") (class "Default")
      (node (ref "D4") (pin "4") (pinfunction "DOUT_4") (pintype "passive"))
      (node (ref "D5") (pin "1") (pinfunction "DIN_1") (pintype "passive"))
    )
    (net (code "37") (name "Net-(D5-DOUT)") (class "Default")
      (node (ref "D5") (pin "4") (pinfunction "DOUT_4") (pintype "passive"))
      (node (ref "D6") (pin "1") (pinfunction "DIN_1") (pintype "passive"))
    )
    (net (code "38") (name "Net-(P3-C11M)") (class "Default")
      (node (ref "C15") (pin "2") (pinfunction "2_2") (pintype "passive"))
      (node (ref "P3") (pin "28") (pinfunction "C11M_28") (pintype "passive"))
    )
    (net (code "39") (name "Net-(P3-C11P)") (class "Default")
      (node (ref "C15") (pin "1") (pinfunction "1_1") (pintype "passive"))
      (node (ref "P3") (pin "29") (pinfunction "C11P_29") (pintype "passive"))
    )
    (net (code "40") (name "Net-(P3-C12M)") (class "Default")
      (node (ref "C13") (pin "2") (pinfunction "2_2") (pintype "passive"))
      (node (ref "P3") (pin "26") (pinfunction "C12M_26") (pintype "passive"))
    )
    (net (code "41") (name "Net-(P3-C12P)") (class "Default")
      (node (ref "C13") (pin "1") (pinfunction "1_1") (pintype "passive"))
      (node (ref "P3") (pin "27") (pinfunction "C12P_27") (pintype "passive"))
    )
    (net (code "42") (name "Net-(P3-C13M)") (class "Default")
      (node (ref "C12") (pin "2") (pinfunction "2_2") (pintype "passive"))
      (node (ref "P3") (pin "24") (pinfunction "C13M_24") (pintype "passive"))
    )
    (net (code "43") (name "Net-(P3-C13P)") (class "Default")
      (node (ref "C12") (pin "1") (pinfunction "1_1") (pintype "passive"))
      (node (ref "P3") (pin "25") (pinfunction "C13P_25") (pintype "passive"))
    )
    (net (code "44") (name "Net-(P3-C14M)") (class "Default")
      (node (ref "C11") (pin "2") (pinfunction "2_2") (pintype "passive"))
      (node (ref "P3") (pin "22") (pinfunction "C14M_22") (pintype "passive"))
    )
    (net (code "45") (name "Net-(P3-C14P)") (class "Default")
      (node (ref "C11") (pin "1") (pinfunction "1_1") (pintype "passive"))
      (node (ref "P3") (pin "23") (pinfunction "C14P_23") (pintype "passive"))
    )
    (net (code "46") (name "Net-(P3-C15M)") (class "Default")
      (node (ref "C10") (pin "2") (pinfunction "2_2") (pintype "passive"))
      (node (ref "P3") (pin "20") (pinfunction "C15M_20") (pintype "passive"))
    )
    (net (code "47") (name "Net-(P3-C15P)") (class "Default")
      (node (ref "C10") (pin "1") (pinfunction "1_1") (pintype "passive"))
      (node (ref "P3") (pin "21") (pinfunction "C15P_21") (pintype "passive"))
    )
    (net (code "48") (name "Net-(P3-C16M)") (class "Default")
      (node (ref "C9") (pin "1") (pinfunction "1_1") (pintype "passive"))
      (node (ref "P3") (pin "18") (pinfunction "C16M_18") (pintype "passive"))
    )
    (net (code "49") (name "Net-(P3-C16P)") (class "Default")
      (node (ref "C9") (pin "2") (pinfunction "2_2") (pintype "passive"))
      (node (ref "P3") (pin "19") (pinfunction "C16P_19") (pintype "passive"))
    )
    (net (code "50") (name "Net-(P3-C21M)") (class "Default")
      (node (ref "C8") (pin "1") (pinfunction "1_1") (pintype "passive"))
      (node (ref "P3") (pin "16") (pinfunction "C21M_16") (pintype "passive"))
    )
    (net (code "51") (name "Net-(P3-C21P)") (class "Default")
      (node (ref "C8") (pin "2") (pinfunction "2_2") (pintype "passive"))
      (node (ref "P3") (pin "17") (pinfunction "C21P_17") (pintype "passive"))
    )
    (net (code "52") (name "Net-(P3-C31M)") (class "Default")
      (node (ref "C7") (pin "1") (pinfunction "1_1") (pintype "passive"))
      (node (ref "P3") (pin "14") (pinfunction "C31M_14") (pintype "passive"))
    )
    (net (code "53") (name "Net-(P3-C31P)") (class "Default")
      (node (ref "C7") (pin "2") (pinfunction "2_2") (pintype "passive"))
      (node (ref "P3") (pin "15") (pinfunction "C31P_15") (pintype "passive"))
    )
    (net (code "54") (name "Net-(P3-C41M)") (class "Default")
      (node (ref "C6") (pin "2") (pinfunction "2_2") (pintype "passive"))
      (node (ref "P3") (pin "13") (pinfunction "C41M_13") (pintype "passive"))
    )
    (net (code "55") (name "Net-(P3-C41P)") (class "Default")
      (node (ref "C6") (pin "1") (pinfunction "1_1") (pintype "passive"))
      (node (ref "P3") (pin "12") (pinfunction "C41P_12") (pintype "passive"))
    )
    (net (code "56") (name "Net-(P3-VCL)") (class "Default")
      (node (ref "C5") (pin "2") (pinfunction "2_2") (pintype "passive"))
      (node (ref "P3") (pin "9") (pinfunction "VCL_9") (pintype "passive"))
    )
    (net (code "57") (name "Net-(P3-VCOM_DRIVER)") (class "Default")
      (node (ref "P3") (pin "30") (pinfunction "VCOM_DRIVER_30") (pintype "passive"))
      (node (ref "R10") (pin "2") (pinfunction "2_2") (pintype "passive"))
    )
    (net (code "58") (name "Net-(P3-VDH)") (class "Default")
      (node (ref "C18") (pin "1") (pinfunction "1_1") (pintype "passive"))
      (node (ref "P3") (pin "36") (pinfunction "VDH_36") (pintype "passive"))
      (node (ref "Q2") (pin "3") (pinfunction "D_3") (pintype "passive"))
    )
    (net (code "59") (name "Net-(P3-VDL)") (class "Default")
      (node (ref "C21") (pin "1") (pinfunction "1_1") (pintype "passive"))
      (node (ref "P3") (pin "37") (pinfunction "VDL_37") (pintype "passive"))
    )
    (net (code "60") (name "Net-(P3-VGH)") (class "Default")
      (node (ref "C16") (pin "1") (pinfunction "1_1") (pintype "passive"))
      (node (ref "P3") (pin "34") (pinfunction "VGH_34") (pintype "passive"))
      (node (ref "Q1") (pin "3") (pinfunction "D_3") (pintype "passive"))
    )
    (net (code "61") (name "Net-(U2-IO1)") (class "Default")
      (node (ref "TP1") (pin "1") (pinfunction "1_1") (pintype "passive"))
      (node (ref "U2") (pin "39") (pinfunction "IO1_39") (pintype "passive"))
    )
    (net (code "62") (name "Net-(U2-IO2)") (class "Default")
      (node (ref "TP2") (pin "1") (pinfunction "1_1") (pintype "passive"))
      (node (ref "U2") (pin "38") (pinfunction "IO2_38") (pintype "passive"))
    )
    (net (code "63") (name "Net-(U2-IO14)") (class "Default")
      (node (ref "TP14") (pin "1") (pinfunction "1_1") (pintype "passive"))
      (node (ref "U2") (pin "22") (pinfunction "IO14_22") (pintype "passive"))
    )
    (net (code "64") (name "Net-(U2-IO35)") (class "Default")
      (node (ref "TP35") (pin "1") (pinfunction "1_1") (pintype "passive"))
      (node (ref "U2") (pin "28") (pinfunction "IO35_28") (pintype "passive"))
    )
    (net (code "65") (name "Net-(U2-IO36)") (class "Default")
      (node (ref "TP36") (pin "1") (pinfunction "1_1") (pintype "passive"))
      (node (ref "U2") (pin "29") (pinfunction "IO36_29") (pintype "passive"))
    )
    (net (code "66") (name "Net-(U2-IO37)") (class "Default")
      (node (ref "TP37") (pin "1") (pinfunction "1_1") (pintype "passive"))
      (node (ref "U2") (pin "30") (pinfunction "IO37_30") (pintype "passive"))
    )
    (net (code "67") (name "Net-(U2-IO39)") (class "Default")
      (node (ref "TP39") (pin "1") (pinfunction "1_1") (pintype "passive"))
      (node (ref "U2") (pin "32") (pinfunction "IO39_32") (pintype "passive"))
    )
    (net (code "68") (name "Net-(U2-IO40)") (class "Default")
      (node (ref "TP40") (pin "1") (pinfunction "1_1") (pintype "passive"))
      (node (ref "U2") (pin "33") (pinfunction "IO40_33") (pintype "passive"))
    )
    (net (code "69") (name "Net-(U2-IO41)") (class "Default")
      (node (ref "TP41") (pin "1") (pinfunction "1_1") (pintype "passive"))
      (node (ref "U2") (pin "34") (pinfunction "IO41_34") (pintype "passive"))
    )
    (net (code "70") (name "Net-(U2-IO42)") (class "Default")
      (node (ref "TP42") (pin "1") (pinfunction "1_1") (pintype "passive"))
      (node (ref "U2") (pin "35") (pinfunction "IO42_35") (pintype "passive"))
    )
    (net (code "71") (name "Net-(U2-IO46)") (class "Default")
      (node (ref "TP46") (pin "1") (pinfunction "1_1") (pintype "passive"))
      (node (ref "U2") (pin "16") (pinfunction "IO46_16") (pintype "passive"))
    )
    (net (code "72") (name "VBAT") (class "Default")
      (node (ref "P5") (pin "5") (pinfunction "5_5") (pintype "passive"))
      (node (ref "S1") (pin "3") (pinfunction "3_3") (pintype "passive"))
    )
    (net (code "73") (name "VCC") (class "Default")
      (node (ref "C2") (pin "1") (pinfunction "1_1") (pintype "passive"))
      (node (ref "S1") (pin "2") (pinfunction "2_2") (pintype "passive"))
      (node (ref "U1") (pin "1") (pinfunction "VIN_1") (pintype "passive"))
    )
    (net (code "74") (name "unconnected-(D6-DOUT-Pad4)") (class "Default")
      (node (ref "D6") (pin "4") (pinfunction "DOUT_4") (pintype "passive+no_connect"))
    )
    (net (code "75") (name "unconnected-(P3-C42M-Pad11)") (class "Default")
      (node (ref "P3") (pin "11") (pinfunction "C42M_11") (pintype "passive+no_connect"))
    )
    (net (code "76") (name "unconnected-(P3-C42P-Pad10)") (class "Default")
      (node (ref "P3") (pin "10") (pinfunction "C42P_10") (pintype "passive+no_connect"))
    )
  )
)
